# lcr.net
KiCad netlist of a schematic drawn in EAGLE
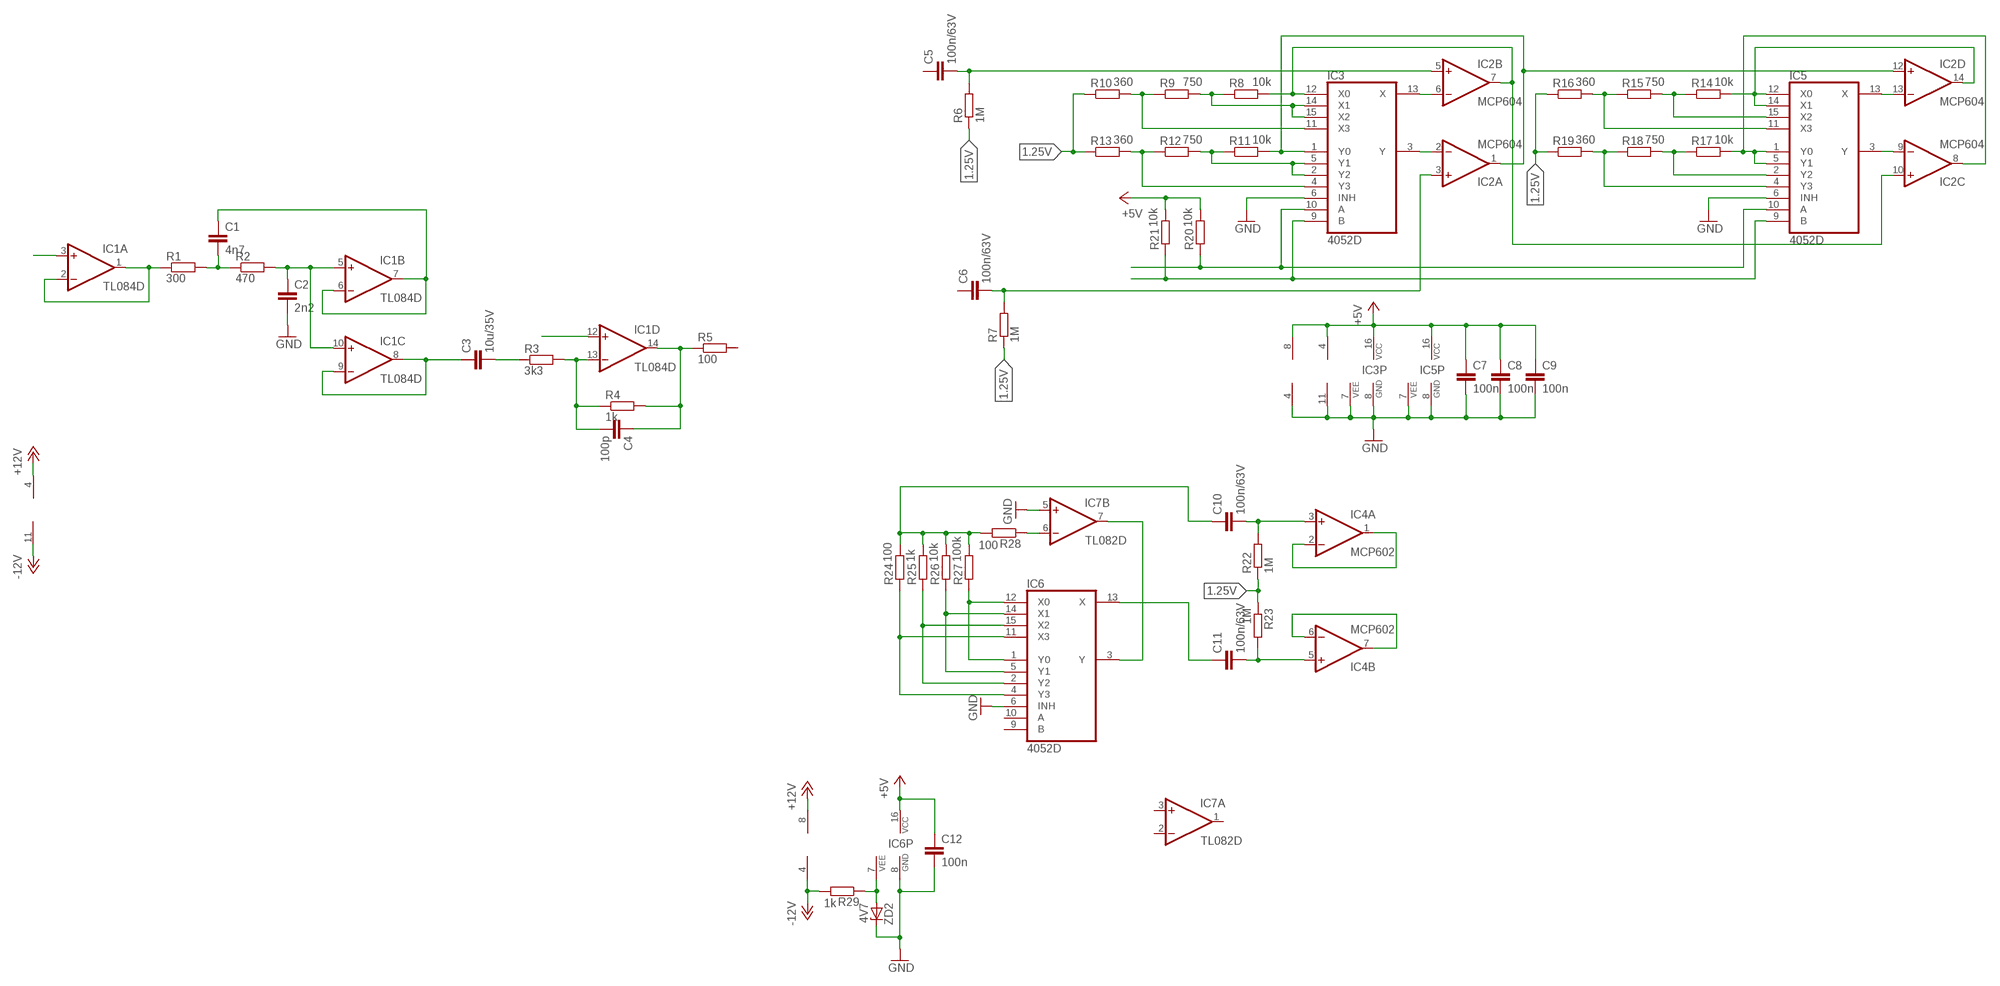
[diagram p0: schematic, sheet 1]

(export (version "E")
  (design (tool "Eeschema 10.0.6"))
  (components
    (comp (ref "C1")
      (value "4n7")
      (footprint "eagle-import:C0603K")
      (libsource (lib "eagle-import") (part "C-EUC0603K"))
    )
    (comp (ref "C2")
      (value "2n2")
      (footprint "eagle-import:C0603K")
      (libsource (lib "eagle-import") (part "C-EUC0603K"))
    )
    (comp (ref "C3")
      (value "10u/35V")
      (footprint "eagle-import:C1206K")
      (libsource (lib "eagle-import") (part "C-EUC1206K"))
    )
    (comp (ref "C4")
      (value "100p")
      (footprint "eagle-import:C0603K")
      (libsource (lib "eagle-import") (part "C-EUC0603K"))
    )
    (comp (ref "C5")
      (value "100n/63V")
      (footprint "eagle-import:C1206K")
      (libsource (lib "eagle-import") (part "C-EUC1206K"))
    )
    (comp (ref "C6")
      (value "100n/63V")
      (footprint "eagle-import:C1206K")
      (libsource (lib "eagle-import") (part "C-EUC1206K"))
    )
    (comp (ref "C7")
      (value "100n")
      (footprint "eagle-import:C0603K")
      (libsource (lib "eagle-import") (part "C-EUC0603K"))
    )
    (comp (ref "C8")
      (value "100n")
      (footprint "eagle-import:C0603K")
      (libsource (lib "eagle-import") (part "C-EUC0603K"))
    )
    (comp (ref "C9")
      (value "100n")
      (footprint "eagle-import:C0603K")
      (libsource (lib "eagle-import") (part "C-EUC0603K"))
    )
    (comp (ref "C10")
      (value "100n/63V")
      (footprint "eagle-import:C1206K")
      (libsource (lib "eagle-import") (part "C-EUC1206K"))
    )
    (comp (ref "C11")
      (value "100n/63V")
      (footprint "eagle-import:C1206K")
      (libsource (lib "eagle-import") (part "C-EUC1206K"))
    )
    (comp (ref "C12")
      (value "100n")
      (footprint "eagle-import:C0603K")
      (libsource (lib "eagle-import") (part "C-EUC0603K"))
    )
    (comp (ref "IC1")
      (value "TL084D")
      (footprint "eagle-import:SO14")
      (libsource (lib "eagle-import") (part "TL084D"))
    )
    (comp (ref "IC2")
      (value "MCP604")
      (footprint "eagle-import:SO14")
      (libsource (lib "eagle-import") (part "TL084D"))
    )
    (comp (ref "IC3")
      (value "4052D")
      (footprint "eagle-import:SO16")
      (libsource (lib "eagle-import") (part "4052D"))
    )
    (comp (ref "IC4")
      (value "MCP602")
      (footprint "eagle-import:SO08")
      (libsource (lib "eagle-import") (part "LM358D"))
    )
    (comp (ref "IC5")
      (value "4052D")
      (footprint "eagle-import:SO16")
      (libsource (lib "eagle-import") (part "4052D"))
    )
    (comp (ref "IC6")
      (value "4052D")
      (footprint "eagle-import:SO16")
      (libsource (lib "eagle-import") (part "4052D"))
    )
    (comp (ref "IC7")
      (value "TL082D")
      (footprint "eagle-import:SO08")
      (libsource (lib "eagle-import") (part "TL082D"))
    )
    (comp (ref "R1")
      (value "300")
      (footprint "eagle-import:R0603")
      (libsource (lib "eagle-import") (part "R-EU_R0603"))
    )
    (comp (ref "R2")
      (value "470")
      (footprint "eagle-import:R0603")
      (libsource (lib "eagle-import") (part "R-EU_R0603"))
    )
    (comp (ref "R3")
      (value "3k3")
      (footprint "eagle-import:R0603")
      (libsource (lib "eagle-import") (part "R-EU_R0603"))
    )
    (comp (ref "R4")
      (value "1k")
      (footprint "eagle-import:R0603")
      (libsource (lib "eagle-import") (part "R-EU_R0603"))
    )
    (comp (ref "R5")
      (value "100")
      (footprint "eagle-import:R0603")
      (libsource (lib "eagle-import") (part "R-EU_R0603"))
    )
    (comp (ref "R6")
      (value "1M")
      (footprint "eagle-import:R0603")
      (libsource (lib "eagle-import") (part "R-EU_R0603"))
    )
    (comp (ref "R7")
      (value "1M")
      (footprint "eagle-import:R0603")
      (libsource (lib "eagle-import") (part "R-EU_R0603"))
    )
    (comp (ref "R8")
      (value "10k")
      (footprint "eagle-import:R0603")
      (libsource (lib "eagle-import") (part "R-EU_R0603"))
    )
    (comp (ref "R9")
      (value "750")
      (footprint "eagle-import:R0603")
      (libsource (lib "eagle-import") (part "R-EU_R0603"))
    )
    (comp (ref "R10")
      (value "360")
      (footprint "eagle-import:R0603")
      (libsource (lib "eagle-import") (part "R-EU_R0603"))
    )
    (comp (ref "R11")
      (value "10k")
      (footprint "eagle-import:R0603")
      (libsource (lib "eagle-import") (part "R-EU_R0603"))
    )
    (comp (ref "R12")
      (value "750")
      (footprint "eagle-import:R0603")
      (libsource (lib "eagle-import") (part "R-EU_R0603"))
    )
    (comp (ref "R13")
      (value "360")
      (footprint "eagle-import:R0603")
      (libsource (lib "eagle-import") (part "R-EU_R0603"))
    )
    (comp (ref "R14")
      (value "10k")
      (footprint "eagle-import:R0603")
      (libsource (lib "eagle-import") (part "R-EU_R0603"))
    )
    (comp (ref "R15")
      (value "750")
      (footprint "eagle-import:R0603")
      (libsource (lib "eagle-import") (part "R-EU_R0603"))
    )
    (comp (ref "R16")
      (value "360")
      (footprint "eagle-import:R0603")
      (libsource (lib "eagle-import") (part "R-EU_R0603"))
    )
    (comp (ref "R17")
      (value "10k")
      (footprint "eagle-import:R0603")
      (libsource (lib "eagle-import") (part "R-EU_R0603"))
    )
    (comp (ref "R18")
      (value "750")
      (footprint "eagle-import:R0603")
      (libsource (lib "eagle-import") (part "R-EU_R0603"))
    )
    (comp (ref "R19")
      (value "360")
      (footprint "eagle-import:R0603")
      (libsource (lib "eagle-import") (part "R-EU_R0603"))
    )
    (comp (ref "R20")
      (value "10k")
      (footprint "eagle-import:R0603")
      (libsource (lib "eagle-import") (part "R-EU_R0603"))
    )
    (comp (ref "R21")
      (value "10k")
      (footprint "eagle-import:R0603")
      (libsource (lib "eagle-import") (part "R-EU_R0603"))
    )
    (comp (ref "R22")
      (value "1M")
      (footprint "eagle-import:R0603")
      (libsource (lib "eagle-import") (part "R-EU_R0603"))
    )
    (comp (ref "R23")
      (value "1M")
      (footprint "eagle-import:R0603")
      (libsource (lib "eagle-import") (part "R-EU_R0603"))
    )
    (comp (ref "R24")
      (value "100")
      (footprint "eagle-import:R0603")
      (libsource (lib "eagle-import") (part "R-EU_R0603"))
    )
    (comp (ref "R25")
      (value "1k")
      (footprint "eagle-import:R0603")
      (libsource (lib "eagle-import") (part "R-EU_R0603"))
    )
    (comp (ref "R26")
      (value "10k")
      (footprint "eagle-import:R0603")
      (libsource (lib "eagle-import") (part "R-EU_R0603"))
    )
    (comp (ref "R27")
      (value "100k")
      (footprint "eagle-import:R0603")
      (libsource (lib "eagle-import") (part "R-EU_R0603"))
    )
    (comp (ref "R28")
      (value "100")
      (footprint "eagle-import:R0603")
      (libsource (lib "eagle-import") (part "R-EU_R0603"))
    )
    (comp (ref "R29")
      (value "1k")
      (footprint "eagle-import:R0603")
      (libsource (lib "eagle-import") (part "R-EU_R0603"))
    )
    (comp (ref "ZD2")
      (value "4V7")
      (footprint "eagle-import:SOT23")
      (libsource (lib "eagle-import") (part "ZD-A1-C3"))
    )
  )
  (nets
    (net (code "1") (name "+5V") (class "Default")
      (node (ref "C12") (pin "1") (pinfunction "1_1") (pintype "passive"))
      (node (ref "C7") (pin "1") (pinfunction "1_1") (pintype "passive"))
      (node (ref "C8") (pin "1") (pinfunction "1_1") (pintype "passive"))
      (node (ref "C9") (pin "1") (pinfunction "1_1") (pintype "passive"))
      (node (ref "IC2") (pin "4") (pinfunction "V+_4") (pintype "power_in"))
      (node (ref "IC3") (pin "16") (pinfunction "VCC_16") (pintype "power_in"))
      (node (ref "IC4") (pin "8") (pinfunction "V+_8") (pintype "power_in"))
      (node (ref "IC5") (pin "16") (pinfunction "VCC_16") (pintype "power_in"))
      (node (ref "IC6") (pin "16") (pinfunction "VCC_16") (pintype "power_in"))
      (node (ref "R20") (pin "2") (pinfunction "2_2") (pintype "passive"))
      (node (ref "R21") (pin "2") (pinfunction "2_2") (pintype "passive"))
    )
    (net (code "2") (name "+12V") (class "Default")
      (node (ref "IC1") (pin "4") (pinfunction "V+_4") (pintype "power_in"))
      (node (ref "IC7") (pin "8") (pinfunction "V+_8") (pintype "power_in"))
    )
    (net (code "3") (name "-12V") (class "Default")
      (node (ref "IC1") (pin "11") (pinfunction "V-_11") (pintype "power_in"))
      (node (ref "IC7") (pin "4") (pinfunction "V-_4") (pintype "power_in"))
      (node (ref "R29") (pin "2") (pinfunction "2_2") (pintype "passive"))
    )
    (net (code "4") (name "1.25V") (class "Default")
      (node (ref "R10") (pin "1") (pinfunction "1_1") (pintype "passive"))
      (node (ref "R13") (pin "1") (pinfunction "1_1") (pintype "passive"))
      (node (ref "R16") (pin "1") (pinfunction "1_1") (pintype "passive"))
      (node (ref "R19") (pin "1") (pinfunction "1_1") (pintype "passive"))
      (node (ref "R22") (pin "1") (pinfunction "1_1") (pintype "passive"))
      (node (ref "R23") (pin "1") (pinfunction "1_1") (pintype "passive"))
      (node (ref "R6") (pin "1") (pinfunction "1_1") (pintype "passive"))
      (node (ref "R7") (pin "1") (pinfunction "1_1") (pintype "passive"))
    )
    (net (code "5") (name "GND") (class "Default")
      (node (ref "C12") (pin "2") (pinfunction "2_2") (pintype "passive"))
      (node (ref "C2") (pin "2") (pinfunction "2_2") (pintype "passive"))
      (node (ref "C7") (pin "2") (pinfunction "2_2") (pintype "passive"))
      (node (ref "C8") (pin "2") (pinfunction "2_2") (pintype "passive"))
      (node (ref "C9") (pin "2") (pinfunction "2_2") (pintype "passive"))
      (node (ref "IC2") (pin "11") (pinfunction "V-_11") (pintype "power_in"))
      (node (ref "IC3") (pin "6") (pinfunction "INH_6") (pintype "input"))
      (node (ref "IC3") (pin "7") (pinfunction "VEE_7") (pintype "power_in"))
      (node (ref "IC3") (pin "8") (pinfunction "GND_8") (pintype "power_in"))
      (node (ref "IC4") (pin "4") (pinfunction "V-_4") (pintype "power_in"))
      (node (ref "IC5") (pin "6") (pinfunction "INH_6") (pintype "input"))
      (node (ref "IC5") (pin "7") (pinfunction "VEE_7") (pintype "power_in"))
      (node (ref "IC5") (pin "8") (pinfunction "GND_8") (pintype "power_in"))
      (node (ref "IC6") (pin "6") (pinfunction "INH_6") (pintype "input"))
      (node (ref "IC6") (pin "8") (pinfunction "GND_8") (pintype "power_in"))
      (node (ref "IC7") (pin "5") (pinfunction "+IN_5") (pintype "input"))
      (node (ref "ZD2") (pin "3") (pinfunction "C_3") (pintype "passive"))
    )
    (net (code "6") (name "Net-(C1-Pad2)") (class "Default")
      (node (ref "C1") (pin "2") (pinfunction "2_2") (pintype "passive"))
      (node (ref "R1") (pin "2") (pinfunction "2_2") (pintype "passive"))
      (node (ref "R2") (pin "1") (pinfunction "1_1") (pintype "passive"))
    )
    (net (code "7") (name "Net-(C3-Pad2)") (class "Default")
      (node (ref "C3") (pin "2") (pinfunction "2_2") (pintype "passive"))
      (node (ref "R3") (pin "1") (pinfunction "1_1") (pintype "passive"))
    )
    (net (code "8") (name "Net-(C10-Pad1)") (class "Default")
      (node (ref "C10") (pin "1") (pinfunction "1_1") (pintype "passive"))
      (node (ref "R24") (pin "2") (pinfunction "2_2") (pintype "passive"))
      (node (ref "R25") (pin "2") (pinfunction "2_2") (pintype "passive"))
      (node (ref "R26") (pin "2") (pinfunction "2_2") (pintype "passive"))
      (node (ref "R27") (pin "2") (pinfunction "2_2") (pintype "passive"))
      (node (ref "R28") (pin "2") (pinfunction "2_2") (pintype "passive"))
    )
    (net (code "9") (name "Net-(IC1A--IN)") (class "Default")
      (node (ref "IC1") (pin "1") (pinfunction "OUT_1") (pintype "output"))
      (node (ref "IC1") (pin "2") (pinfunction "-IN_2") (pintype "input"))
      (node (ref "R1") (pin "1") (pinfunction "1_1") (pintype "passive"))
    )
    (net (code "10") (name "Net-(IC1B-+IN)") (class "Default")
      (node (ref "C2") (pin "1") (pinfunction "1_1") (pintype "passive"))
      (node (ref "IC1") (pin "10") (pinfunction "+IN_10") (pintype "input"))
      (node (ref "IC1") (pin "5") (pinfunction "+IN_5") (pintype "input"))
      (node (ref "R2") (pin "2") (pinfunction "2_2") (pintype "passive"))
    )
    (net (code "11") (name "Net-(IC1B--IN)") (class "Default")
      (node (ref "C1") (pin "1") (pinfunction "1_1") (pintype "passive"))
      (node (ref "IC1") (pin "6") (pinfunction "-IN_6") (pintype "input"))
      (node (ref "IC1") (pin "7") (pinfunction "OUT_7") (pintype "output"))
    )
    (net (code "12") (name "Net-(IC1C--IN)") (class "Default")
      (node (ref "C3") (pin "1") (pinfunction "1_1") (pintype "passive"))
      (node (ref "IC1") (pin "8") (pinfunction "OUT_8") (pintype "output"))
      (node (ref "IC1") (pin "9") (pinfunction "-IN_9") (pintype "input"))
    )
    (net (code "13") (name "Net-(IC1D--IN)") (class "Default")
      (node (ref "C4") (pin "2") (pinfunction "2_2") (pintype "passive"))
      (node (ref "IC1") (pin "13") (pinfunction "-IN_13") (pintype "input"))
      (node (ref "R3") (pin "2") (pinfunction "2_2") (pintype "passive"))
      (node (ref "R4") (pin "1") (pinfunction "1_1") (pintype "passive"))
    )
    (net (code "14") (name "Net-(IC1D-OUT)") (class "Default")
      (node (ref "C4") (pin "1") (pinfunction "1_1") (pintype "passive"))
      (node (ref "IC1") (pin "14") (pinfunction "OUT_14") (pintype "output"))
      (node (ref "R4") (pin "2") (pinfunction "2_2") (pintype "passive"))
      (node (ref "R5") (pin "1") (pinfunction "1_1") (pintype "passive"))
    )
    (net (code "15") (name "Net-(IC2A-+IN)") (class "Default")
      (node (ref "C6") (pin "2") (pinfunction "2_2") (pintype "passive"))
      (node (ref "IC2") (pin "3") (pinfunction "+IN_3") (pintype "input"))
      (node (ref "R7") (pin "2") (pinfunction "2_2") (pintype "passive"))
    )
    (net (code "16") (name "Net-(IC2A--IN)") (class "Default")
      (node (ref "IC2") (pin "2") (pinfunction "-IN_2") (pintype "input"))
      (node (ref "IC3") (pin "3") (pinfunction "Y_3") (pintype "bidirectional"))
    )
    (net (code "17") (name "Net-(IC2A-OUT)") (class "Default")
      (node (ref "IC2") (pin "1") (pinfunction "OUT_1") (pintype "output"))
      (node (ref "IC2") (pin "12") (pinfunction "+IN_12") (pintype "input"))
      (node (ref "IC3") (pin "1") (pinfunction "Y0_1") (pintype "bidirectional"))
      (node (ref "R11") (pin "2") (pinfunction "2_2") (pintype "passive"))
    )
    (net (code "18") (name "Net-(IC2B-+IN)") (class "Default")
      (node (ref "C5") (pin "2") (pinfunction "2_2") (pintype "passive"))
      (node (ref "IC2") (pin "5") (pinfunction "+IN_5") (pintype "input"))
      (node (ref "R6") (pin "2") (pinfunction "2_2") (pintype "passive"))
    )
    (net (code "19") (name "Net-(IC2B--IN)") (class "Default")
      (node (ref "IC2") (pin "6") (pinfunction "-IN_6") (pintype "input"))
      (node (ref "IC3") (pin "13") (pinfunction "X_13") (pintype "bidirectional"))
    )
    (net (code "20") (name "Net-(IC2B-OUT)") (class "Default")
      (node (ref "IC2") (pin "10") (pinfunction "+IN_10") (pintype "input"))
      (node (ref "IC2") (pin "7") (pinfunction "OUT_7") (pintype "output"))
      (node (ref "IC3") (pin "12") (pinfunction "X0_12") (pintype "bidirectional"))
      (node (ref "R8") (pin "2") (pinfunction "2_2") (pintype "passive"))
    )
    (net (code "21") (name "Net-(IC2C--IN)") (class "Default")
      (node (ref "IC2") (pin "9") (pinfunction "-IN_9") (pintype "input"))
      (node (ref "IC5") (pin "3") (pinfunction "Y_3") (pintype "bidirectional"))
    )
    (net (code "22") (name "Net-(IC2C-OUT)") (class "Default")
      (node (ref "IC2") (pin "8") (pinfunction "OUT_8") (pintype "output"))
      (node (ref "IC5") (pin "1") (pinfunction "Y0_1") (pintype "bidirectional"))
      (node (ref "IC5") (pin "5") (pinfunction "Y1_5") (pintype "bidirectional"))
      (node (ref "R17") (pin "2") (pinfunction "2_2") (pintype "passive"))
    )
    (net (code "23") (name "Net-(IC2D--IN)") (class "Default")
      (node (ref "IC2") (pin "13") (pinfunction "-IN_13") (pintype "input"))
      (node (ref "IC5") (pin "13") (pinfunction "X_13") (pintype "bidirectional"))
    )
    (net (code "24") (name "Net-(IC2D-OUT)") (class "Default")
      (node (ref "IC2") (pin "14") (pinfunction "OUT_14") (pintype "output"))
      (node (ref "IC5") (pin "12") (pinfunction "X0_12") (pintype "bidirectional"))
      (node (ref "IC5") (pin "14") (pinfunction "X1_14") (pintype "bidirectional"))
      (node (ref "R14") (pin "2") (pinfunction "2_2") (pintype "passive"))
    )
    (net (code "25") (name "Net-(IC3A-A)") (class "Default")
      (node (ref "IC3") (pin "10") (pinfunction "A_10") (pintype "input"))
      (node (ref "IC5") (pin "10") (pinfunction "A_10") (pintype "input"))
      (node (ref "R20") (pin "1") (pinfunction "1_1") (pintype "passive"))
    )
    (net (code "26") (name "Net-(IC3A-B)") (class "Default")
      (node (ref "IC3") (pin "9") (pinfunction "B_9") (pintype "input"))
      (node (ref "IC5") (pin "9") (pinfunction "B_9") (pintype "input"))
      (node (ref "R21") (pin "1") (pinfunction "1_1") (pintype "passive"))
    )
    (net (code "27") (name "Net-(IC3A-X1)") (class "Default")
      (node (ref "IC3") (pin "14") (pinfunction "X1_14") (pintype "bidirectional"))
      (node (ref "IC3") (pin "15") (pinfunction "X2_15") (pintype "bidirectional"))
      (node (ref "R8") (pin "1") (pinfunction "1_1") (pintype "passive"))
      (node (ref "R9") (pin "2") (pinfunction "2_2") (pintype "passive"))
    )
    (net (code "28") (name "Net-(IC3A-X3)") (class "Default")
      (node (ref "IC3") (pin "11") (pinfunction "X3_11") (pintype "bidirectional"))
      (node (ref "R10") (pin "2") (pinfunction "2_2") (pintype "passive"))
      (node (ref "R9") (pin "1") (pinfunction "1_1") (pintype "passive"))
    )
    (net (code "29") (name "Net-(IC3A-Y1)") (class "Default")
      (node (ref "IC3") (pin "2") (pinfunction "Y2_2") (pintype "bidirectional"))
      (node (ref "IC3") (pin "5") (pinfunction "Y1_5") (pintype "bidirectional"))
      (node (ref "R11") (pin "1") (pinfunction "1_1") (pintype "passive"))
      (node (ref "R12") (pin "2") (pinfunction "2_2") (pintype "passive"))
    )
    (net (code "30") (name "Net-(IC3A-Y3)") (class "Default")
      (node (ref "IC3") (pin "4") (pinfunction "Y3_4") (pintype "bidirectional"))
      (node (ref "R12") (pin "1") (pinfunction "1_1") (pintype "passive"))
      (node (ref "R13") (pin "2") (pinfunction "2_2") (pintype "passive"))
    )
    (net (code "31") (name "Net-(IC4A-+IN)") (class "Default")
      (node (ref "C10") (pin "2") (pinfunction "2_2") (pintype "passive"))
      (node (ref "IC4") (pin "3") (pinfunction "+IN_3") (pintype "input"))
      (node (ref "R22") (pin "2") (pinfunction "2_2") (pintype "passive"))
    )
    (net (code "32") (name "Net-(IC4A--IN)") (class "Default")
      (node (ref "IC4") (pin "1") (pinfunction "OUT_1") (pintype "output"))
      (node (ref "IC4") (pin "2") (pinfunction "-IN_2") (pintype "input"))
    )
    (net (code "33") (name "Net-(IC4B-+IN)") (class "Default")
      (node (ref "C11") (pin "2") (pinfunction "2_2") (pintype "passive"))
      (node (ref "IC4") (pin "5") (pinfunction "+IN_5") (pintype "input"))
      (node (ref "R23") (pin "2") (pinfunction "2_2") (pintype "passive"))
    )
    (net (code "34") (name "Net-(IC4B--IN)") (class "Default")
      (node (ref "IC4") (pin "6") (pinfunction "-IN_6") (pintype "input"))
      (node (ref "IC4") (pin "7") (pinfunction "OUT_7") (pintype "output"))
    )
    (net (code "35") (name "Net-(IC5A-X2)") (class "Default")
      (node (ref "IC5") (pin "15") (pinfunction "X2_15") (pintype "bidirectional"))
      (node (ref "R14") (pin "1") (pinfunction "1_1") (pintype "passive"))
      (node (ref "R15") (pin "2") (pinfunction "2_2") (pintype "passive"))
    )
    (net (code "36") (name "Net-(IC5A-X3)") (class "Default")
      (node (ref "IC5") (pin "11") (pinfunction "X3_11") (pintype "bidirectional"))
      (node (ref "R15") (pin "1") (pinfunction "1_1") (pintype "passive"))
      (node (ref "R16") (pin "2") (pinfunction "2_2") (pintype "passive"))
    )
    (net (code "37") (name "Net-(IC5A-Y2)") (class "Default")
      (node (ref "IC5") (pin "2") (pinfunction "Y2_2") (pintype "bidirectional"))
      (node (ref "R17") (pin "1") (pinfunction "1_1") (pintype "passive"))
      (node (ref "R18") (pin "2") (pinfunction "2_2") (pintype "passive"))
    )
    (net (code "38") (name "Net-(IC5A-Y3)") (class "Default")
      (node (ref "IC5") (pin "4") (pinfunction "Y3_4") (pintype "bidirectional"))
      (node (ref "R18") (pin "1") (pinfunction "1_1") (pintype "passive"))
      (node (ref "R19") (pin "2") (pinfunction "2_2") (pintype "passive"))
    )
    (net (code "39") (name "Net-(IC6A-X)") (class "Default")
      (node (ref "C11") (pin "1") (pinfunction "1_1") (pintype "passive"))
      (node (ref "IC6") (pin "13") (pinfunction "X_13") (pintype "bidirectional"))
    )
    (net (code "40") (name "Net-(IC6A-X0)") (class "Default")
      (node (ref "IC6") (pin "1") (pinfunction "Y0_1") (pintype "bidirectional"))
      (node (ref "IC6") (pin "12") (pinfunction "X0_12") (pintype "bidirectional"))
      (node (ref "R27") (pin "1") (pinfunction "1_1") (pintype "passive"))
    )
    (net (code "41") (name "Net-(IC6A-X1)") (class "Default")
      (node (ref "IC6") (pin "14") (pinfunction "X1_14") (pintype "bidirectional"))
      (node (ref "IC6") (pin "5") (pinfunction "Y1_5") (pintype "bidirectional"))
      (node (ref "R26") (pin "1") (pinfunction "1_1") (pintype "passive"))
    )
    (net (code "42") (name "Net-(IC6A-X2)") (class "Default")
      (node (ref "IC6") (pin "15") (pinfunction "X2_15") (pintype "bidirectional"))
      (node (ref "IC6") (pin "2") (pinfunction "Y2_2") (pintype "bidirectional"))
      (node (ref "R25") (pin "1") (pinfunction "1_1") (pintype "passive"))
    )
    (net (code "43") (name "Net-(IC6A-X3)") (class "Default")
      (node (ref "IC6") (pin "11") (pinfunction "X3_11") (pintype "bidirectional"))
      (node (ref "IC6") (pin "4") (pinfunction "Y3_4") (pintype "bidirectional"))
      (node (ref "R24") (pin "1") (pinfunction "1_1") (pintype "passive"))
    )
    (net (code "44") (name "Net-(IC6A-Y)") (class "Default")
      (node (ref "IC6") (pin "3") (pinfunction "Y_3") (pintype "bidirectional"))
      (node (ref "IC7") (pin "7") (pinfunction "OUT_7") (pintype "output"))
    )
    (net (code "45") (name "Net-(IC6B-VEE)") (class "Default")
      (node (ref "IC6") (pin "7") (pinfunction "VEE_7") (pintype "power_in"))
      (node (ref "R29") (pin "1") (pinfunction "1_1") (pintype "passive"))
      (node (ref "ZD2") (pin "1") (pinfunction "A_1") (pintype "passive"))
    )
    (net (code "46") (name "Net-(IC7B--IN)") (class "Default")
      (node (ref "IC7") (pin "6") (pinfunction "-IN_6") (pintype "input"))
      (node (ref "R28") (pin "1") (pinfunction "1_1") (pintype "passive"))
    )
    (net (code "47") (name "unconnected-(C5-Pad1)") (class "Default")
      (node (ref "C5") (pin "1") (pinfunction "1_1") (pintype "passive"))
    )
    (net (code "48") (name "unconnected-(C6-Pad1)") (class "Default")
      (node (ref "C6") (pin "1") (pinfunction "1_1") (pintype "passive"))
    )
    (net (code "49") (name "unconnected-(IC1A-+IN-Pad3)") (class "Default")
      (node (ref "IC1") (pin "3") (pinfunction "+IN_3") (pintype "input"))
    )
    (net (code "50") (name "unconnected-(IC1D-+IN-Pad12)") (class "Default")
      (node (ref "IC1") (pin "12") (pinfunction "+IN_12") (pintype "input"))
    )
    (net (code "51") (name "unconnected-(IC6A-A-Pad10)") (class "Default")
      (node (ref "IC6") (pin "10") (pinfunction "A_10") (pintype "input"))
    )
    (net (code "52") (name "unconnected-(IC6A-B-Pad9)") (class "Default")
      (node (ref "IC6") (pin "9") (pinfunction "B_9") (pintype "input"))
    )
    (net (code "53") (name "unconnected-(IC7A-+IN-Pad3)") (class "Default")
      (node (ref "IC7") (pin "3") (pinfunction "+IN_3") (pintype "input"))
    )
    (net (code "54") (name "unconnected-(IC7A--IN-Pad2)") (class "Default")
      (node (ref "IC7") (pin "2") (pinfunction "-IN_2") (pintype "input"))
    )
    (net (code "55") (name "unconnected-(IC7A-OUT-Pad1)") (class "Default")
      (node (ref "IC7") (pin "1") (pinfunction "OUT_1") (pintype "output"))
    )
    (net (code "56") (name "unconnected-(R5-Pad2)") (class "Default")
      (node (ref "R5") (pin "2") (pinfunction "2_2") (pintype "passive"))
    )
  )
)
